# ESP32_mainboard.net
KiCad netlist of a schematic drawn in EAGLE
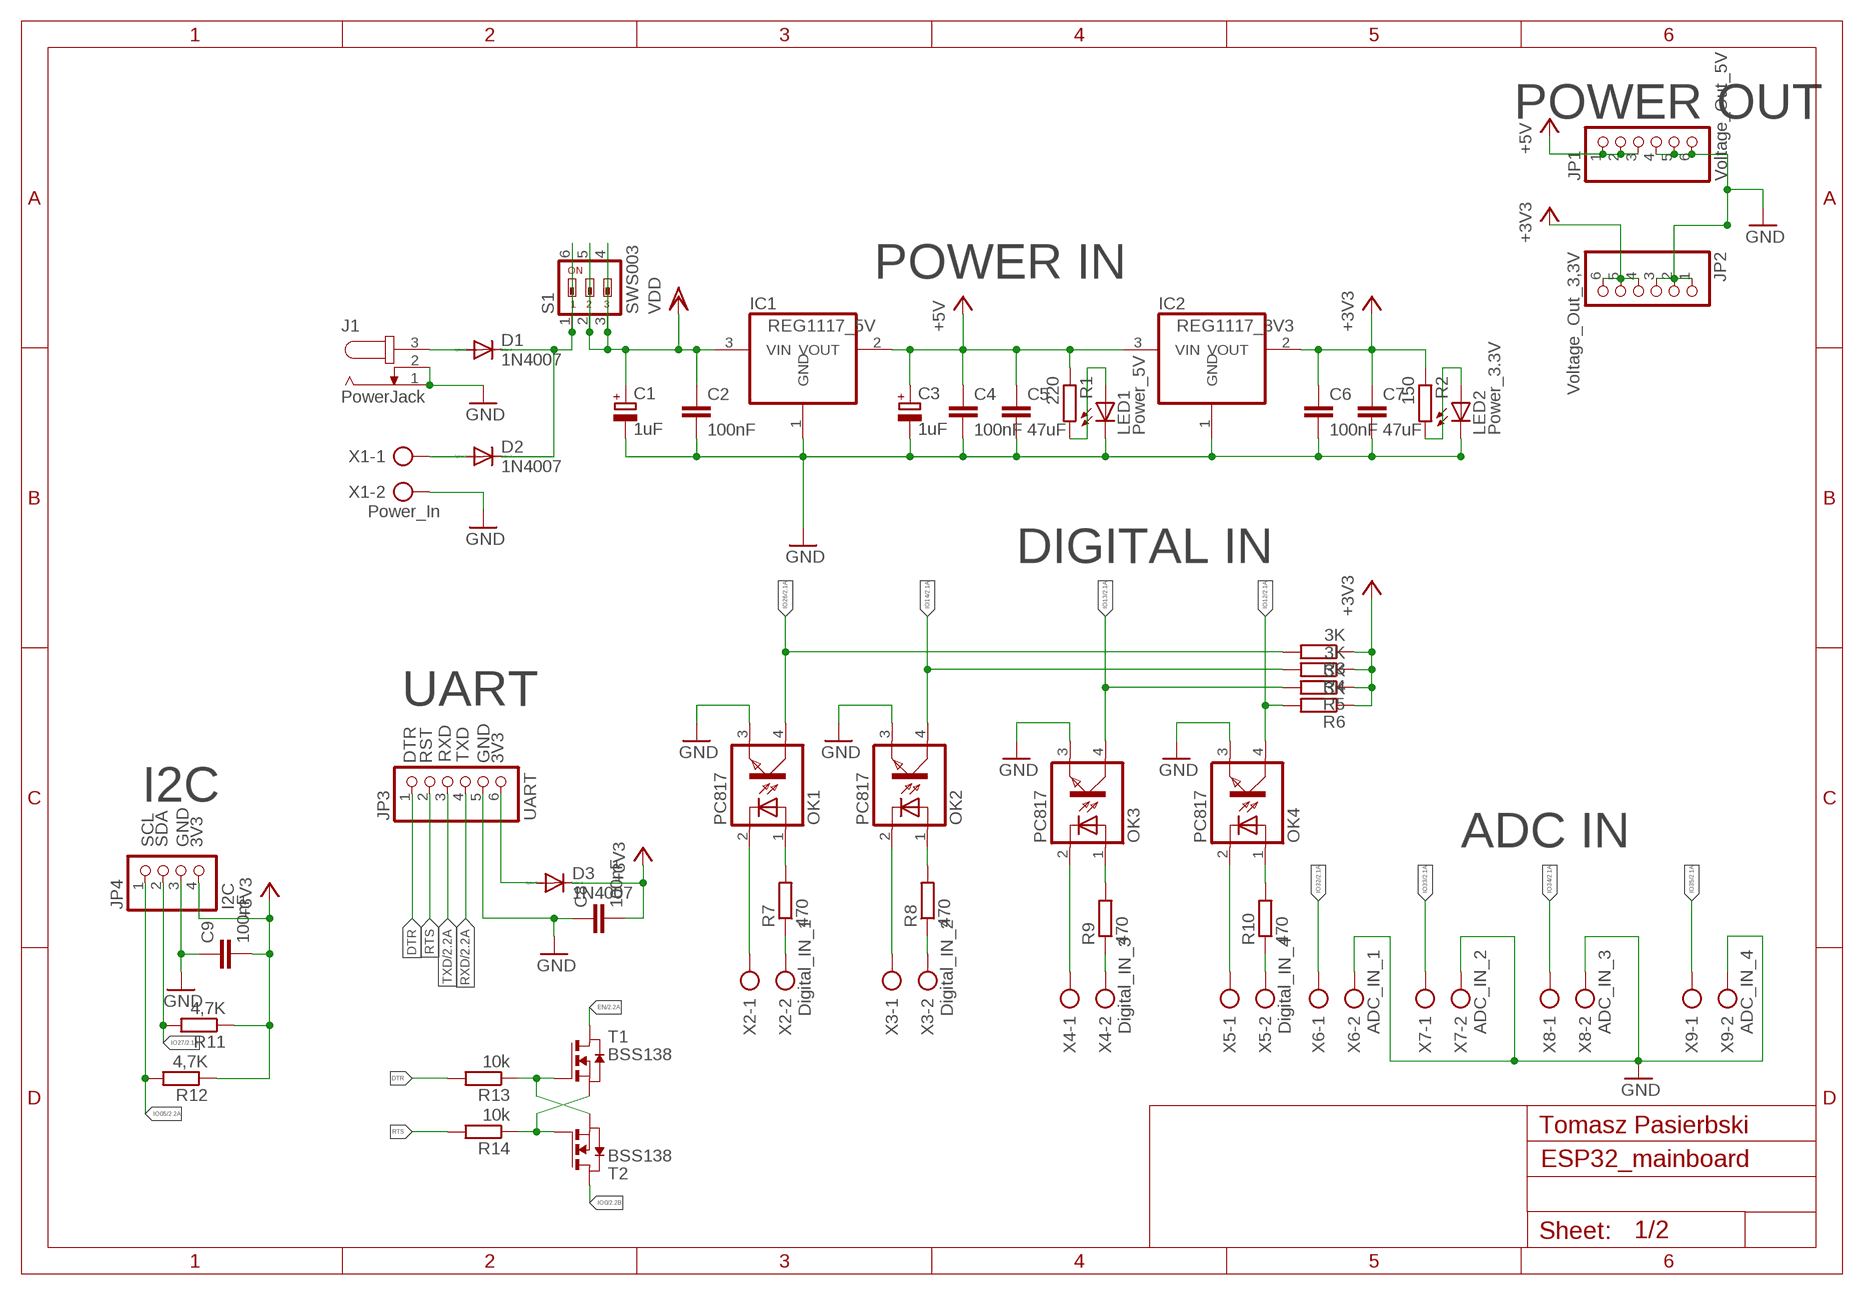
[diagram p0: schematic, sheet 1]
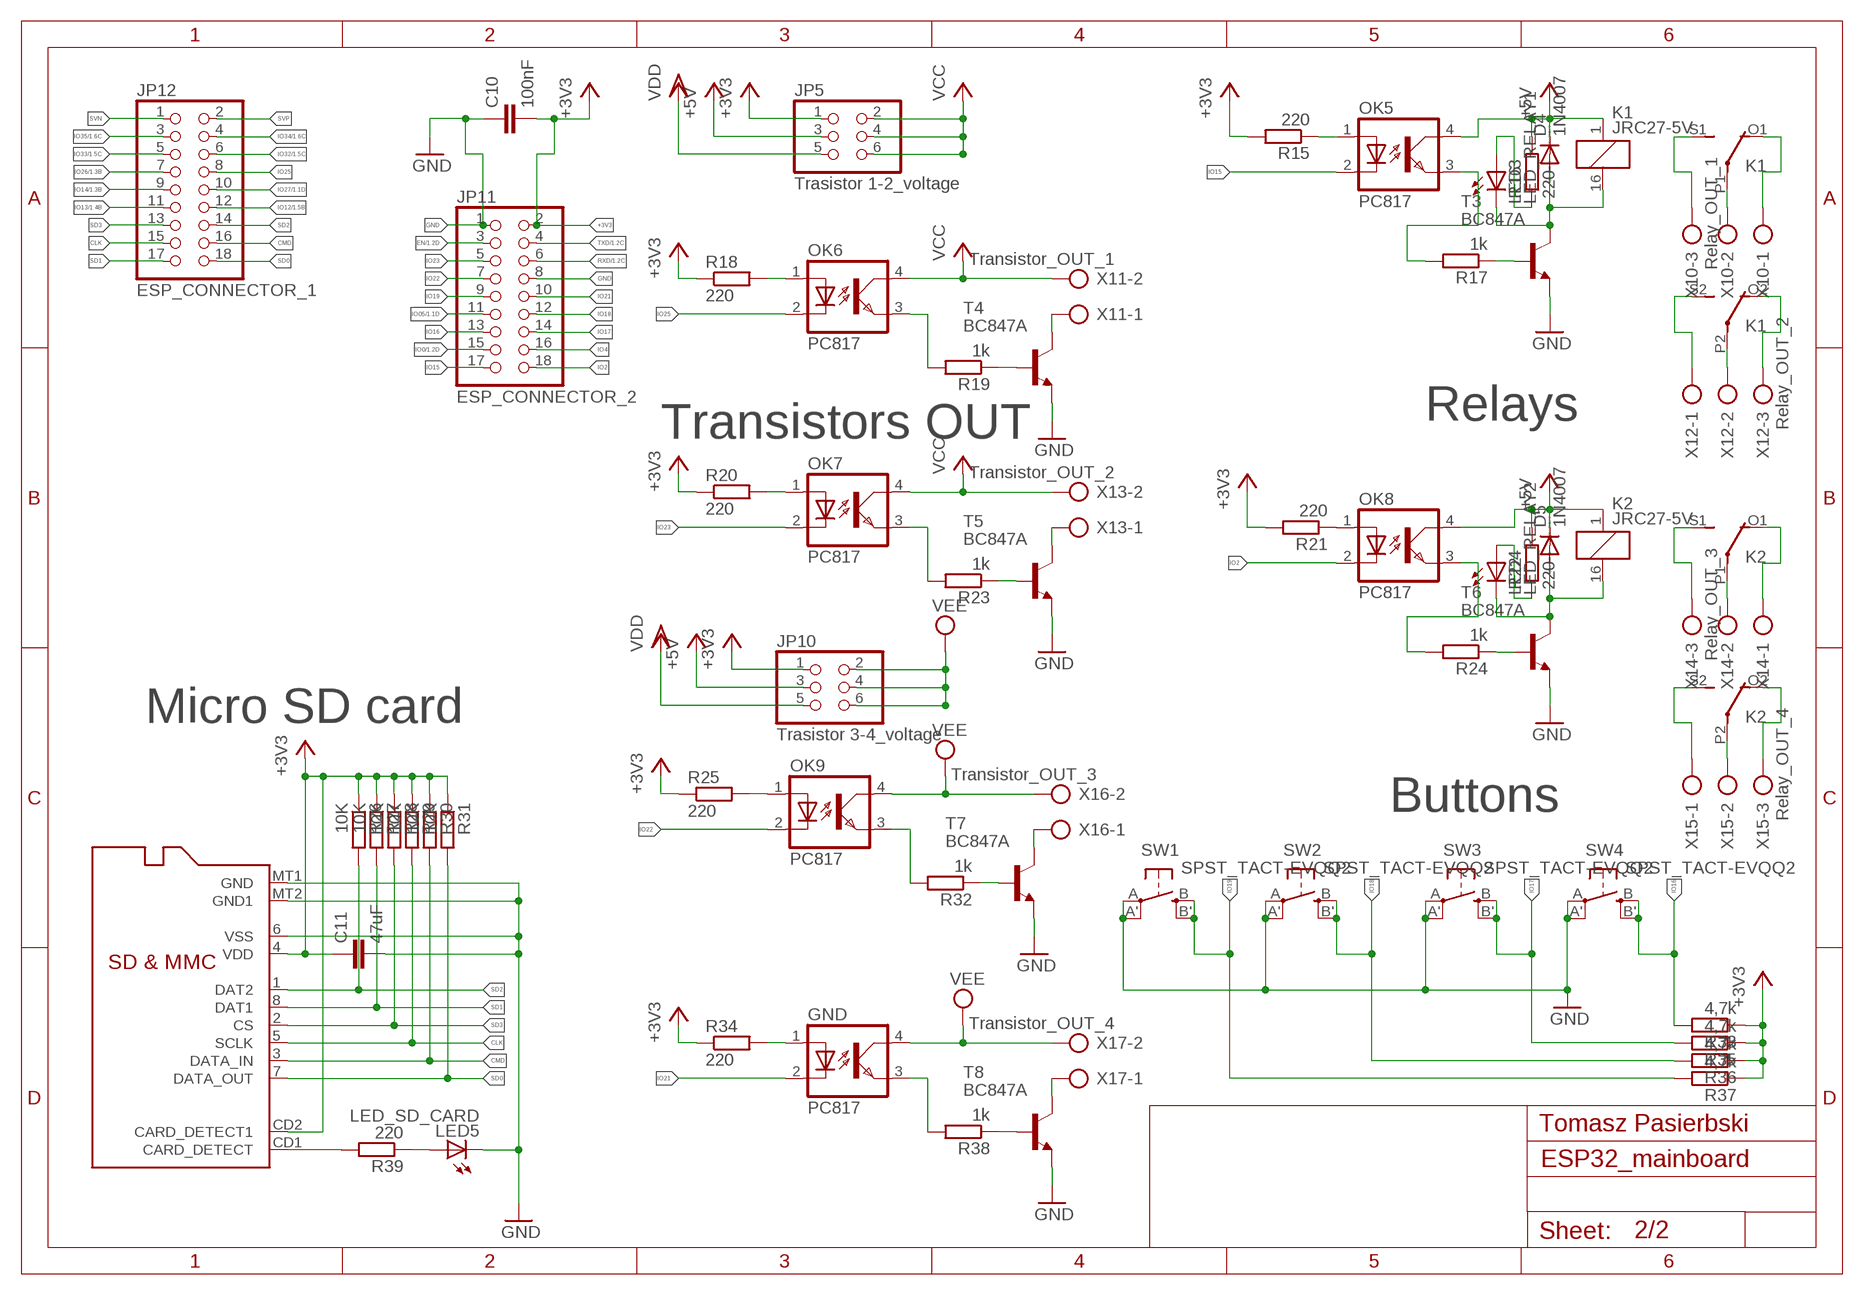
[diagram p1: schematic, sheet 2]

(export (version "E")
  (design (tool "Eeschema 10.0.6"))
  (components
    (comp (ref "C1")
      (value "1uF")
      (footprint "eagle-import:140CLH-0810")
      (libsource (lib "eagle-import") (part "CPOL-EU140CLH-0810"))
    )
    (comp (ref "C2")
      (value "100nF")
      (footprint "eagle-import:C1206")
      (libsource (lib "eagle-import") (part "C-EUC1206"))
    )
    (comp (ref "C3")
      (value "1uF")
      (footprint "eagle-import:140CLH-0810")
      (libsource (lib "eagle-import") (part "CPOL-EU140CLH-0810"))
    )
    (comp (ref "C4")
      (value "100nF")
      (footprint "eagle-import:C1206")
      (libsource (lib "eagle-import") (part "C-EUC1206"))
    )
    (comp (ref "C5")
      (value "47uF")
      (footprint "eagle-import:C1808")
      (libsource (lib "eagle-import") (part "C-EUC1808"))
    )
    (comp (ref "C6")
      (value "100nF")
      (footprint "eagle-import:C1206")
      (libsource (lib "eagle-import") (part "C-EUC1206"))
    )
    (comp (ref "C7")
      (value "47uF")
      (footprint "eagle-import:C1808")
      (libsource (lib "eagle-import") (part "C-EUC1808"))
    )
    (comp (ref "C8")
      (value "100nF")
      (footprint "eagle-import:C1206")
      (libsource (lib "eagle-import") (part "C-EUC1206"))
    )
    (comp (ref "C9")
      (value "100nF")
      (footprint "eagle-import:C1206")
      (libsource (lib "eagle-import") (part "C-EUC1206"))
    )
    (comp (ref "D1")
      (value "1N4007")
      (footprint "eagle-import:DO214AA")
      (libsource (lib "eagle-import") (part "DIODE-DO214AA"))
    )
    (comp (ref "D2")
      (value "1N4007")
      (footprint "eagle-import:DO214AA")
      (libsource (lib "eagle-import") (part "DIODE-DO214AA"))
    )
    (comp (ref "D3")
      (value "1N4007")
      (footprint "eagle-import:DO214AA")
      (libsource (lib "eagle-import") (part "DIODE-DO214AA"))
    )
    (comp (ref "IC1")
      (value "REG1117_5V")
      (footprint "eagle-import:SOT223")
      (fields (field (name "MPN") "REG1117"))
      (libsource (lib "eagle-import") (part "REG1117"))
    )
    (comp (ref "IC2")
      (value "REG1117_3V3")
      (footprint "eagle-import:SOT223")
      (fields (field (name "MPN") "REG1117"))
      (libsource (lib "eagle-import") (part "REG1117"))
    )
    (comp (ref "J1")
      (value "PowerJack")
      (footprint "eagle-import:SPC4077")
      (libsource (lib "eagle-import") (part "JACK-PLUG0"))
    )
    (comp (ref "JP1")
      (value "Voltage_Out_5V")
      (footprint "eagle-import:1X06_90")
      (libsource (lib "eagle-import") (part "PINHD-1X6/90"))
    )
    (comp (ref "JP2")
      (value "Voltage_Out_3,3V")
      (footprint "eagle-import:1X06_90")
      (libsource (lib "eagle-import") (part "PINHD-1X6/90"))
    )
    (comp (ref "JP3")
      (value "UART")
      (footprint "eagle-import:1X06_90")
      (libsource (lib "eagle-import") (part "PINHD-1X6/90"))
    )
    (comp (ref "JP4")
      (value "I2C")
      (footprint "eagle-import:1X04_90")
      (libsource (lib "eagle-import") (part "PINHD-1X4/90"))
    )
    (comp (ref "LED1")
      (value "Power_5V")
      (footprint "eagle-import:CHIPLED_1206")
      (libsource (lib "eagle-import") (part "LEDCHIPLED_1206"))
    )
    (comp (ref "LED2")
      (value "Power_3.3V")
      (footprint "eagle-import:CHIPLED_1206")
      (libsource (lib "eagle-import") (part "LEDCHIPLED_1206"))
    )
    (comp (ref "OK1")
      (value "PC817")
      (footprint "eagle-import:DIL04")
      (fields (field (name "MPN") "PC817X4J000F"))
      (libsource (lib "eagle-import") (part "PC817"))
    )
    (comp (ref "OK2")
      (value "PC817")
      (footprint "eagle-import:DIL04")
      (fields (field (name "MPN") "PC817X4J000F"))
      (libsource (lib "eagle-import") (part "PC817"))
    )
    (comp (ref "OK3")
      (value "PC817")
      (footprint "eagle-import:DIL04")
      (fields (field (name "MPN") "PC817X4J000F"))
      (libsource (lib "eagle-import") (part "PC817"))
    )
    (comp (ref "OK4")
      (value "PC817")
      (footprint "eagle-import:DIL04")
      (fields (field (name "MPN") "PC817X4J000F"))
      (libsource (lib "eagle-import") (part "PC817"))
    )
    (comp (ref "R1")
      (value "220")
      (footprint "eagle-import:M1206")
      (libsource (lib "eagle-import") (part "R-EU_M1206"))
    )
    (comp (ref "R2")
      (value "150")
      (footprint "eagle-import:M1206")
      (libsource (lib "eagle-import") (part "R-EU_M1206"))
    )
    (comp (ref "R3")
      (value "3K")
      (footprint "eagle-import:M1206")
      (libsource (lib "eagle-import") (part "R-EU_M1206"))
    )
    (comp (ref "R4")
      (value "3K")
      (footprint "eagle-import:M1206")
      (libsource (lib "eagle-import") (part "R-EU_M1206"))
    )
    (comp (ref "R5")
      (value "3K")
      (footprint "eagle-import:M1206")
      (libsource (lib "eagle-import") (part "R-EU_M1206"))
    )
    (comp (ref "R6")
      (value "3K")
      (footprint "eagle-import:M1206")
      (libsource (lib "eagle-import") (part "R-EU_M1206"))
    )
    (comp (ref "R7")
      (value "470")
      (footprint "eagle-import:M1206")
      (libsource (lib "eagle-import") (part "R-EU_M1206"))
    )
    (comp (ref "R8")
      (value "470")
      (footprint "eagle-import:M1206")
      (libsource (lib "eagle-import") (part "R-EU_M1206"))
    )
    (comp (ref "R9")
      (value "470")
      (footprint "eagle-import:M1206")
      (libsource (lib "eagle-import") (part "R-EU_M1206"))
    )
    (comp (ref "R10")
      (value "470")
      (footprint "eagle-import:M1206")
      (libsource (lib "eagle-import") (part "R-EU_M1206"))
    )
    (comp (ref "R11")
      (value "4,7K")
      (footprint "eagle-import:M1206")
      (libsource (lib "eagle-import") (part "R-EU_M1206"))
    )
    (comp (ref "R12")
      (value "4,7K")
      (footprint "eagle-import:M1206")
      (libsource (lib "eagle-import") (part "R-EU_M1206"))
    )
    (comp (ref "R13")
      (value "10k")
      (footprint "eagle-import:M1206")
      (libsource (lib "eagle-import") (part "R-EU_M1206"))
    )
    (comp (ref "R14")
      (value "10k")
      (footprint "eagle-import:M1206")
      (libsource (lib "eagle-import") (part "R-EU_M1206"))
    )
    (comp (ref "S1")
      (value "SWS003")
      (footprint "eagle-import:SMS-003")
      (libsource (lib "eagle-import") (part "SWS003"))
    )
    (comp (ref "T1")
      (value "BSS138")
      (footprint "eagle-import:SOT-23")
      (libsource (lib "eagle-import") (part "NMOSSOT23"))
    )
    (comp (ref "T2")
      (value "BSS138")
      (footprint "eagle-import:SOT-23")
      (libsource (lib "eagle-import") (part "NMOSSOT23"))
    )
    (comp (ref "X1")
      (value "Power_In")
      (footprint "eagle-import:AK300_2")
      (libsource (lib "eagle-import") (part "AK300/2"))
    )
    (comp (ref "X2")
      (value "Digital_IN_1")
      (footprint "eagle-import:AK300_2")
      (libsource (lib "eagle-import") (part "AK300/2"))
    )
    (comp (ref "X3")
      (value "Digital_IN_2")
      (footprint "eagle-import:AK300_2")
      (libsource (lib "eagle-import") (part "AK300/2"))
    )
    (comp (ref "X4")
      (value "Digital_IN_3")
      (footprint "eagle-import:AK300_2")
      (libsource (lib "eagle-import") (part "AK300/2"))
    )
    (comp (ref "X5")
      (value "Digital_IN_4")
      (footprint "eagle-import:AK300_2")
      (libsource (lib "eagle-import") (part "AK300/2"))
    )
    (comp (ref "X6")
      (value "ADC_IN_1")
      (footprint "eagle-import:AK300_2")
      (libsource (lib "eagle-import") (part "AK300/2"))
    )
    (comp (ref "X7")
      (value "ADC_IN_2")
      (footprint "eagle-import:AK300_2")
      (libsource (lib "eagle-import") (part "AK300/2"))
    )
    (comp (ref "X8")
      (value "ADC_IN_3")
      (footprint "eagle-import:AK300_2")
      (libsource (lib "eagle-import") (part "AK300/2"))
    )
    (comp (ref "X9")
      (value "ADC_IN_4")
      (footprint "eagle-import:AK300_2")
      (libsource (lib "eagle-import") (part "AK300/2"))
    )
    (comp (ref "C10")
      (value "100nF")
      (footprint "eagle-import:C1206")
      (libsource (lib "eagle-import") (part "C-EUC1206"))
    )
    (comp (ref "C11")
      (value "47uF")
      (footprint "eagle-import:C1808")
      (libsource (lib "eagle-import") (part "C-EUC1808"))
    )
    (comp (ref "D4")
      (value "1N4007")
      (footprint "eagle-import:DO214AC")
      (libsource (lib "eagle-import") (part "DIODE-DO214AC"))
    )
    (comp (ref "D5")
      (value "1N4007")
      (footprint "eagle-import:DO214AC")
      (libsource (lib "eagle-import") (part "DIODE-DO214AC"))
    )
    (comp (ref "GND")
      (value "PC817")
      (footprint "eagle-import:DIL04")
      (fields (field (name "MPN") "PC817X4J000F"))
      (libsource (lib "eagle-import") (part "PC817"))
    )
    (comp (ref "JP5")
      (value "Trasistor 1-2_voltage")
      (footprint "eagle-import:2X03")
      (libsource (lib "eagle-import") (part "PINHD-2X3"))
    )
    (comp (ref "JP10")
      (value "Trasistor 3-4_voltage")
      (footprint "eagle-import:2X03")
      (libsource (lib "eagle-import") (part "PINHD-2X3"))
    )
    (comp (ref "JP11")
      (value "ESP_CONNECTOR_2")
      (footprint "eagle-import:2X09")
      (libsource (lib "eagle-import") (part "PINHD-2X9"))
    )
    (comp (ref "JP12")
      (value "ESP_CONNECTOR_1")
      (footprint "eagle-import:2X09")
      (libsource (lib "eagle-import") (part "PINHD-2X9"))
    )
    (comp (ref "K1")
      (value "JRC27-5V")
      (footprint "eagle-import:351")
      (libsource (lib "eagle-import") (part "351"))
    )
    (comp (ref "K2")
      (value "JRC27-5V")
      (footprint "eagle-import:351")
      (libsource (lib "eagle-import") (part "351"))
    )
    (comp (ref "LED3")
      (value "LED_RELAY1")
      (footprint "eagle-import:CHIPLED_1206")
      (libsource (lib "eagle-import") (part "LEDCHIPLED_1206"))
    )
    (comp (ref "LED4")
      (value "LED_RELAY2")
      (footprint "eagle-import:CHIPLED_1206")
      (libsource (lib "eagle-import") (part "LEDCHIPLED_1206"))
    )
    (comp (ref "LED5")
      (value "LED_SD_CARD")
      (footprint "eagle-import:CHIPLED_1206")
      (libsource (lib "eagle-import") (part "LEDCHIPLED_1206"))
    )
    (comp (ref "OK5")
      (value "PC817")
      (footprint "eagle-import:DIL04")
      (fields (field (name "MPN") "PC817X4J000F"))
      (libsource (lib "eagle-import") (part "PC817"))
    )
    (comp (ref "OK6")
      (value "PC817")
      (footprint "eagle-import:DIL04")
      (fields (field (name "MPN") "PC817X4J000F"))
      (libsource (lib "eagle-import") (part "PC817"))
    )
    (comp (ref "OK7")
      (value "PC817")
      (footprint "eagle-import:DIL04")
      (fields (field (name "MPN") "PC817X4J000F"))
      (libsource (lib "eagle-import") (part "PC817"))
    )
    (comp (ref "OK8")
      (value "PC817")
      (footprint "eagle-import:DIL04")
      (fields (field (name "MPN") "PC817X4J000F"))
      (libsource (lib "eagle-import") (part "PC817"))
    )
    (comp (ref "OK9")
      (value "PC817")
      (footprint "eagle-import:DIL04")
      (fields (field (name "MPN") "PC817X4J000F"))
      (libsource (lib "eagle-import") (part "PC817"))
    )
    (comp (ref "R15")
      (value "220")
      (footprint "eagle-import:M1206")
      (libsource (lib "eagle-import") (part "R-EU_M1206"))
    )
    (comp (ref "R16")
      (value "220")
      (footprint "eagle-import:M1206")
      (libsource (lib "eagle-import") (part "R-EU_M1206"))
    )
    (comp (ref "R17")
      (value "1k")
      (footprint "eagle-import:M1206")
      (libsource (lib "eagle-import") (part "R-EU_M1206"))
    )
    (comp (ref "R18")
      (value "220")
      (footprint "eagle-import:M1206")
      (libsource (lib "eagle-import") (part "R-EU_M1206"))
    )
    (comp (ref "R19")
      (value "1k")
      (footprint "eagle-import:M1206")
      (libsource (lib "eagle-import") (part "R-EU_M1206"))
    )
    (comp (ref "R20")
      (value "220")
      (footprint "eagle-import:M1206")
      (libsource (lib "eagle-import") (part "R-EU_M1206"))
    )
    (comp (ref "R21")
      (value "220")
      (footprint "eagle-import:M1206")
      (libsource (lib "eagle-import") (part "R-EU_M1206"))
    )
    (comp (ref "R22")
      (value "220")
      (footprint "eagle-import:M1206")
      (libsource (lib "eagle-import") (part "R-EU_M1206"))
    )
    (comp (ref "R23")
      (value "1k")
      (footprint "eagle-import:M1206")
      (libsource (lib "eagle-import") (part "R-EU_M1206"))
    )
    (comp (ref "R24")
      (value "1k")
      (footprint "eagle-import:M1206")
      (libsource (lib "eagle-import") (part "R-EU_M1206"))
    )
    (comp (ref "R25")
      (value "220")
      (footprint "eagle-import:M1206")
      (libsource (lib "eagle-import") (part "R-EU_M1206"))
    )
    (comp (ref "R26")
      (value "10K")
      (footprint "eagle-import:M1206")
      (libsource (lib "eagle-import") (part "R-EU_M1206"))
    )
    (comp (ref "R27")
      (value "10K")
      (footprint "eagle-import:M1206")
      (libsource (lib "eagle-import") (part "R-EU_M1206"))
    )
    (comp (ref "R28")
      (value "10K")
      (footprint "eagle-import:M1206")
      (libsource (lib "eagle-import") (part "R-EU_M1206"))
    )
    (comp (ref "R29")
      (value "10K")
      (footprint "eagle-import:M1206")
      (libsource (lib "eagle-import") (part "R-EU_M1206"))
    )
    (comp (ref "R30")
      (value "10K")
      (footprint "eagle-import:M1206")
      (libsource (lib "eagle-import") (part "R-EU_M1206"))
    )
    (comp (ref "R31")
      (value "10K")
      (footprint "eagle-import:M1206")
      (libsource (lib "eagle-import") (part "R-EU_M1206"))
    )
    (comp (ref "R32")
      (value "1k")
      (footprint "eagle-import:M1206")
      (libsource (lib "eagle-import") (part "R-EU_M1206"))
    )
    (comp (ref "R33")
      (value "4,7k")
      (footprint "eagle-import:M1206")
      (libsource (lib "eagle-import") (part "R-EU_M1206"))
    )
    (comp (ref "R34")
      (value "220")
      (footprint "eagle-import:M1206")
      (libsource (lib "eagle-import") (part "R-EU_M1206"))
    )
    (comp (ref "R35")
      (value "4,7k")
      (footprint "eagle-import:M1206")
      (libsource (lib "eagle-import") (part "R-EU_M1206"))
    )
    (comp (ref "R36")
      (value "4,7k")
      (footprint "eagle-import:M1206")
      (libsource (lib "eagle-import") (part "R-EU_M1206"))
    )
    (comp (ref "R37")
      (value "4,7k")
      (footprint "eagle-import:M1206")
      (libsource (lib "eagle-import") (part "R-EU_M1206"))
    )
    (comp (ref "R38")
      (value "1k")
      (footprint "eagle-import:M1206")
      (libsource (lib "eagle-import") (part "R-EU_M1206"))
    )
    (comp (ref "R39")
      (value "220")
      (footprint "eagle-import:M1206")
      (libsource (lib "eagle-import") (part "R-EU_M1206"))
    )
    (comp (ref "SW1")
      (value "SPST_TACT-EVQQ2")
      (footprint "eagle-import:EVQ-Q2")
      (libsource (lib "eagle-import") (part "SPST_TACT-EVQQ2"))
    )
    (comp (ref "SW2")
      (value "SPST_TACT-EVQQ2")
      (footprint "eagle-import:EVQ-Q2")
      (libsource (lib "eagle-import") (part "SPST_TACT-EVQQ2"))
    )
    (comp (ref "SW3")
      (value "SPST_TACT-EVQQ2")
      (footprint "eagle-import:EVQ-Q2")
      (libsource (lib "eagle-import") (part "SPST_TACT-EVQQ2"))
    )
    (comp (ref "SW4")
      (value "SPST_TACT-EVQQ2")
      (footprint "eagle-import:EVQ-Q2")
      (libsource (lib "eagle-import") (part "SPST_TACT-EVQQ2"))
    )
    (comp (ref "T3")
      (value "BC847A")
      (footprint "eagle-import:SOT23-BEC")
      (libsource (lib "eagle-import") (part "-NPN-SOT23-BECBC847"))
    )
    (comp (ref "T4")
      (value "BC847A")
      (footprint "eagle-import:SOT23-BEC")
      (libsource (lib "eagle-import") (part "-NPN-SOT23-BECBC847"))
    )
    (comp (ref "T5")
      (value "BC847A")
      (footprint "eagle-import:SOT23-BEC")
      (libsource (lib "eagle-import") (part "-NPN-SOT23-BECBC847"))
    )
    (comp (ref "T6")
      (value "BC847A")
      (footprint "eagle-import:SOT23-BEC")
      (libsource (lib "eagle-import") (part "-NPN-SOT23-BECBC847"))
    )
    (comp (ref "T7")
      (value "BC847A")
      (footprint "eagle-import:SOT23-BEC")
      (libsource (lib "eagle-import") (part "-NPN-SOT23-BECBC847"))
    )
    (comp (ref "T8")
      (value "BC847A")
      (footprint "eagle-import:SOT23-BEC")
      (libsource (lib "eagle-import") (part "-NPN-SOT23-BECBC847"))
    )
    (comp (ref "U2")
      (value "MICROSD")
      (footprint "eagle-import:MICROSD")
      (libsource (lib "eagle-import") (part "MICROSD"))
    )
    (comp (ref "X10")
      (value "Relay_OUT_1")
      (footprint "eagle-import:AK300_3")
      (libsource (lib "eagle-import") (part "AK300/3"))
    )
    (comp (ref "X11")
      (value "Transistor_OUT_1")
      (footprint "eagle-import:AK300_2")
      (libsource (lib "eagle-import") (part "AK300/2"))
    )
    (comp (ref "X12")
      (value "Relay_OUT_2")
      (footprint "eagle-import:AK300_3")
      (libsource (lib "eagle-import") (part "AK300/3"))
    )
    (comp (ref "X13")
      (value "Transistor_OUT_2")
      (footprint "eagle-import:AK300_2")
      (libsource (lib "eagle-import") (part "AK300/2"))
    )
    (comp (ref "X14")
      (value "Relay_OUT_3")
      (footprint "eagle-import:AK300_3")
      (libsource (lib "eagle-import") (part "AK300/3"))
    )
    (comp (ref "X15")
      (value "Relay_OUT_4")
      (footprint "eagle-import:AK300_3")
      (libsource (lib "eagle-import") (part "AK300/3"))
    )
    (comp (ref "X16")
      (value "Transistor_OUT_3")
      (footprint "eagle-import:AK300_2")
      (libsource (lib "eagle-import") (part "AK300/2"))
    )
    (comp (ref "X17")
      (value "Transistor_OUT_4")
      (footprint "eagle-import:AK300_2")
      (libsource (lib "eagle-import") (part "AK300/2"))
    )
  )
  (nets
    (net (code "1") (name "+3V3") (class "Default")
      (node (ref "C10") (pin "2") (pinfunction "2_2") (pintype "passive"))
      (node (ref "C11") (pin "1") (pinfunction "1_1") (pintype "passive"))
      (node (ref "C6") (pin "1") (pinfunction "1_1") (pintype "passive"))
      (node (ref "C7") (pin "1") (pinfunction "1_1") (pintype "passive"))
      (node (ref "C8") (pin "2") (pinfunction "2_2") (pintype "passive"))
      (node (ref "C9") (pin "2") (pinfunction "2_2") (pintype "passive"))
      (node (ref "D3") (pin "C") (pinfunction "C_C") (pintype "passive"))
      (node (ref "IC2") (pin "2") (pinfunction "VOUT_2") (pintype "output"))
      (node (ref "JP10") (pin "1") (pinfunction "1_1") (pintype "passive"))
      (node (ref "JP11") (pin "2") (pinfunction "2_2") (pintype "passive"))
      (node (ref "JP2") (pin "4") (pinfunction "4_4") (pintype "passive"))
      (node (ref "JP2") (pin "5") (pinfunction "5_5") (pintype "passive"))
      (node (ref "JP2") (pin "6") (pinfunction "6_6") (pintype "passive"))
      (node (ref "JP4") (pin "4") (pinfunction "4_4") (pintype "passive"))
      (node (ref "JP5") (pin "1") (pinfunction "1_1") (pintype "passive"))
      (node (ref "R11") (pin "1") (pinfunction "1_1") (pintype "passive"))
      (node (ref "R12") (pin "1") (pinfunction "1_1") (pintype "passive"))
      (node (ref "R15") (pin "2") (pinfunction "2_2") (pintype "passive"))
      (node (ref "R18") (pin "1") (pinfunction "1_1") (pintype "passive"))
      (node (ref "R2") (pin "1") (pinfunction "1_1") (pintype "passive"))
      (node (ref "R20") (pin "1") (pinfunction "1_1") (pintype "passive"))
      (node (ref "R21") (pin "2") (pinfunction "2_2") (pintype "passive"))
      (node (ref "R25") (pin "1") (pinfunction "1_1") (pintype "passive"))
      (node (ref "R26") (pin "1") (pinfunction "1_1") (pintype "passive"))
      (node (ref "R27") (pin "1") (pinfunction "1_1") (pintype "passive"))
      (node (ref "R28") (pin "1") (pinfunction "1_1") (pintype "passive"))
      (node (ref "R29") (pin "1") (pinfunction "1_1") (pintype "passive"))
      (node (ref "R3") (pin "1") (pinfunction "1_1") (pintype "passive"))
      (node (ref "R30") (pin "1") (pinfunction "1_1") (pintype "passive"))
      (node (ref "R31") (pin "1") (pinfunction "1_1") (pintype "passive"))
      (node (ref "R33") (pin "1") (pinfunction "1_1") (pintype "passive"))
      (node (ref "R34") (pin "1") (pinfunction "1_1") (pintype "passive"))
      (node (ref "R35") (pin "1") (pinfunction "1_1") (pintype "passive"))
      (node (ref "R36") (pin "1") (pinfunction "1_1") (pintype "passive"))
      (node (ref "R37") (pin "1") (pinfunction "1_1") (pintype "passive"))
      (node (ref "R4") (pin "1") (pinfunction "1_1") (pintype "passive"))
      (node (ref "R5") (pin "1") (pinfunction "1_1") (pintype "passive"))
      (node (ref "R6") (pin "1") (pinfunction "1_1") (pintype "passive"))
      (node (ref "U2") (pin "4") (pinfunction "VDD_4") (pintype "power_in"))
      (node (ref "U2") (pin "CD2") (pinfunction "CARD_DETECT1_CD2") (pintype "passive"))
    )
    (net (code "2") (name "+5V") (class "Default")
      (node (ref "C3") (pin "+") (pinfunction "+_+") (pintype "passive"))
      (node (ref "C4") (pin "1") (pinfunction "1_1") (pintype "passive"))
      (node (ref "C5") (pin "1") (pinfunction "1_1") (pintype "passive"))
      (node (ref "D4") (pin "C") (pinfunction "C_C") (pintype "passive"))
      (node (ref "D5") (pin "C") (pinfunction "C_C") (pintype "passive"))
      (node (ref "IC1") (pin "2") (pinfunction "VOUT_2") (pintype "output"))
      (node (ref "IC2") (pin "3") (pinfunction "VIN_3") (pintype "input"))
      (node (ref "JP1") (pin "1") (pinfunction "1_1") (pintype "passive"))
      (node (ref "JP1") (pin "2") (pinfunction "2_2") (pintype "passive"))
      (node (ref "JP1") (pin "3") (pinfunction "3_3") (pintype "passive"))
      (node (ref "JP10") (pin "3") (pinfunction "3_3") (pintype "passive"))
      (node (ref "JP5") (pin "3") (pinfunction "3_3") (pintype "passive"))
      (node (ref "K1") (pin "1") (pinfunction "1_1") (pintype "passive"))
      (node (ref "K2") (pin "1") (pinfunction "1_1") (pintype "passive"))
      (node (ref "OK5") (pin "4") (pinfunction "COL_4") (pintype "passive"))
      (node (ref "OK8") (pin "4") (pinfunction "COL_4") (pintype "passive"))
      (node (ref "R1") (pin "1") (pinfunction "1_1") (pintype "passive"))
      (node (ref "R16") (pin "2") (pinfunction "2_2") (pintype "passive"))
      (node (ref "R22") (pin "2") (pinfunction "2_2") (pintype "passive"))
    )
    (net (code "3") (name "CLK") (class "Default")
      (node (ref "JP12") (pin "15") (pinfunction "15_15") (pintype "passive"))
      (node (ref "R29") (pin "2") (pinfunction "2_2") (pintype "passive"))
      (node (ref "U2") (pin "5") (pinfunction "SCLK_5") (pintype "input"))
    )
    (net (code "4") (name "CMD") (class "Default")
      (node (ref "JP12") (pin "16") (pinfunction "16_16") (pintype "passive"))
      (node (ref "R30") (pin "2") (pinfunction "2_2") (pintype "passive"))
      (node (ref "U2") (pin "3") (pinfunction "DATA_IN_3") (pintype "input"))
    )
    (net (code "5") (name "DTR") (class "Default")
      (node (ref "JP3") (pin "1") (pinfunction "1_1") (pintype "passive"))
      (node (ref "R13") (pin "2") (pinfunction "2_2") (pintype "passive"))
    )
    (net (code "6") (name "EN") (class "Default")
      (node (ref "JP11") (pin "3") (pinfunction "3_3") (pintype "passive"))
      (node (ref "T1") (pin "1") (pinfunction "D_1") (pintype "passive"))
    )
    (net (code "7") (name "GND") (class "Default")
      (node (ref "C1") (pin "-") (pinfunction "-_-") (pintype "passive"))
      (node (ref "C10") (pin "1") (pinfunction "1_1") (pintype "passive"))
      (node (ref "C11") (pin "2") (pinfunction "2_2") (pintype "passive"))
      (node (ref "C2") (pin "2") (pinfunction "2_2") (pintype "passive"))
      (node (ref "C3") (pin "-") (pinfunction "-_-") (pintype "passive"))
      (node (ref "C4") (pin "2") (pinfunction "2_2") (pintype "passive"))
      (node (ref "C5") (pin "2") (pinfunction "2_2") (pintype "passive"))
      (node (ref "C6") (pin "2") (pinfunction "2_2") (pintype "passive"))
      (node (ref "C7") (pin "2") (pinfunction "2_2") (pintype "passive"))
      (node (ref "C8") (pin "1") (pinfunction "1_1") (pintype "passive"))
      (node (ref "C9") (pin "1") (pinfunction "1_1") (pintype "passive"))
      (node (ref "IC1") (pin "1") (pinfunction "GND_1") (pintype "power_in"))
      (node (ref "IC2") (pin "1") (pinfunction "GND_1") (pintype "power_in"))
      (node (ref "J1") (pin "1") (pinfunction "1_1") (pintype "passive"))
      (node (ref "J1") (pin "2") (pinfunction "2_2") (pintype "passive"))
      (node (ref "JP1") (pin "4") (pinfunction "4_4") (pintype "passive"))
      (node (ref "JP1") (pin "5") (pinfunction "5_5") (pintype "passive"))
      (node (ref "JP1") (pin "6") (pinfunction "6_6") (pintype "passive"))
      (node (ref "JP11") (pin "1") (pinfunction "1_1") (pintype "passive"))
      (node (ref "JP11") (pin "8") (pinfunction "8_8") (pintype "passive"))
      (node (ref "JP2") (pin "1") (pinfunction "1_1") (pintype "passive"))
      (node (ref "JP2") (pin "2") (pinfunction "2_2") (pintype "passive"))
      (node (ref "JP2") (pin "3") (pinfunction "3_3") (pintype "passive"))
      (node (ref "JP3") (pin "5") (pinfunction "5_5") (pintype "passive"))
      (node (ref "JP4") (pin "3") (pinfunction "3_3") (pintype "passive"))
      (node (ref "LED1") (pin "C") (pinfunction "C_C") (pintype "passive"))
      (node (ref "LED2") (pin "C") (pinfunction "C_C") (pintype "passive"))
      (node (ref "LED5") (pin "C") (pinfunction "C_C") (pintype "passive"))
      (node (ref "OK1") (pin "3") (pinfunction "EMIT_3") (pintype "passive"))
      (node (ref "OK2") (pin "3") (pinfunction "EMIT_3") (pintype "passive"))
      (node (ref "OK3") (pin "3") (pinfunction "EMIT_3") (pintype "passive"))
      (node (ref "OK4") (pin "3") (pinfunction "EMIT_3") (pintype "passive"))
      (node (ref "SW1") (pin "A") (pinfunction "P_A") (pintype "passive"))
      (node (ref "SW1") (pin "A'") (pinfunction "P1_A'") (pintype "passive"))
      (node (ref "SW2") (pin "A") (pinfunction "P_A") (pintype "passive"))
      (node (ref "SW2") (pin "A'") (pinfunction "P1_A'") (pintype "passive"))
      (node (ref "SW3") (pin "A") (pinfunction "P_A") (pintype "passive"))
      (node (ref "SW3") (pin "A'") (pinfunction "P1_A'") (pintype "passive"))
      (node (ref "SW4") (pin "A") (pinfunction "P_A") (pintype "passive"))
      (node (ref "SW4") (pin "A'") (pinfunction "P1_A'") (pintype "passive"))
      (node (ref "T3") (pin "E") (pinfunction "E_E") (pintype "passive"))
      (node (ref "T4") (pin "E") (pinfunction "E_E") (pintype "passive"))
      (node (ref "T5") (pin "E") (pinfunction "E_E") (pintype "passive"))
      (node (ref "T6") (pin "E") (pinfunction "E_E") (pintype "passive"))
      (node (ref "T7") (pin "E") (pinfunction "E_E") (pintype "passive"))
      (node (ref "T8") (pin "E") (pinfunction "E_E") (pintype "passive"))
      (node (ref "U2") (pin "6") (pinfunction "VSS_6") (pintype "power_in"))
      (node (ref "U2") (pin "MT1") (pinfunction "GND_MT1") (pintype "power_in"))
      (node (ref "U2") (pin "MT2") (pinfunction "GND1_MT2") (pintype "power_in"))
      (node (ref "X1") (pin "2") (pinfunction "KL_2") (pintype "passive"))
      (node (ref "X6") (pin "2") (pinfunction "KL_2") (pintype "passive"))
      (node (ref "X7") (pin "2") (pinfunction "KL_2") (pintype "passive"))
      (node (ref "X8") (pin "2") (pinfunction "KL_2") (pintype "passive"))
      (node (ref "X9") (pin "2") (pinfunction "KL_2") (pintype "passive"))
    )
    (net (code "8") (name "IO0") (class "Default")
      (node (ref "JP11") (pin "15") (pinfunction "15_15") (pintype "passive"))
      (node (ref "T2") (pin "1") (pinfunction "D_1") (pintype "passive"))
    )
    (net (code "9") (name "IO2") (class "Default")
      (node (ref "JP11") (pin "18") (pinfunction "18_18") (pintype "passive"))
      (node (ref "OK8") (pin "2") (pinfunction "C_2") (pintype "passive"))
    )
    (net (code "10") (name "IO4") (class "Default")
      (node (ref "JP11") (pin "16") (pinfunction "16_16") (pintype "passive"))
    )
    (net (code "11") (name "IO05") (class "Default")
      (node (ref "JP11") (pin "11") (pinfunction "11_11") (pintype "passive"))
      (node (ref "JP4") (pin "1") (pinfunction "1_1") (pintype "passive"))
      (node (ref "R12") (pin "2") (pinfunction "2_2") (pintype "passive"))
    )
    (net (code "12") (name "IO12") (class "Default")
      (node (ref "JP12") (pin "12") (pinfunction "12_12") (pintype "passive"))
      (node (ref "OK4") (pin "4") (pinfunction "COL_4") (pintype "passive"))
      (node (ref "R6") (pin "2") (pinfunction "2_2") (pintype "passive"))
    )
    (net (code "13") (name "IO13") (class "Default")
      (node (ref "JP12") (pin "11") (pinfunction "11_11") (pintype "passive"))
      (node (ref "OK3") (pin "4") (pinfunction "COL_4") (pintype "passive"))
      (node (ref "R5") (pin "2") (pinfunction "2_2") (pintype "passive"))
    )
    (net (code "14") (name "IO14") (class "Default")
      (node (ref "JP12") (pin "9") (pinfunction "9_9") (pintype "passive"))
      (node (ref "OK2") (pin "4") (pinfunction "COL_4") (pintype "passive"))
      (node (ref "R4") (pin "2") (pinfunction "2_2") (pintype "passive"))
    )
    (net (code "15") (name "IO15") (class "Default")
      (node (ref "JP11") (pin "17") (pinfunction "17_17") (pintype "passive"))
      (node (ref "OK5") (pin "2") (pinfunction "C_2") (pintype "passive"))
    )
    (net (code "16") (name "IO16") (class "Default")
      (node (ref "JP11") (pin "13") (pinfunction "13_13") (pintype "passive"))
      (node (ref "R33") (pin "2") (pinfunction "2_2") (pintype "passive"))
      (node (ref "SW4") (pin "B") (pinfunction "S_B") (pintype "passive"))
      (node (ref "SW4") (pin "B'") (pinfunction "S1_B'") (pintype "passive"))
    )
    (net (code "17") (name "IO17") (class "Default")
      (node (ref "JP11") (pin "14") (pinfunction "14_14") (pintype "passive"))
      (node (ref "R35") (pin "2") (pinfunction "2_2") (pintype "passive"))
      (node (ref "SW3") (pin "B") (pinfunction "S_B") (pintype "passive"))
      (node (ref "SW3") (pin "B'") (pinfunction "S1_B'") (pintype "passive"))
    )
    (net (code "18") (name "IO18") (class "Default")
      (node (ref "JP11") (pin "12") (pinfunction "12_12") (pintype "passive"))
      (node (ref "R36") (pin "2") (pinfunction "2_2") (pintype "passive"))
      (node (ref "SW2") (pin "B") (pinfunction "S_B") (pintype "passive"))
      (node (ref "SW2") (pin "B'") (pinfunction "S1_B'") (pintype "passive"))
    )
    (net (code "19") (name "IO19") (class "Default")
      (node (ref "JP11") (pin "9") (pinfunction "9_9") (pintype "passive"))
      (node (ref "R37") (pin "2") (pinfunction "2_2") (pintype "passive"))
      (node (ref "SW1") (pin "B") (pinfunction "S_B") (pintype "passive"))
      (node (ref "SW1") (pin "B'") (pinfunction "S1_B'") (pintype "passive"))
    )
    (net (code "20") (name "IO21") (class "Default")
      (node (ref "GND") (pin "2") (pinfunction "C_2") (pintype "passive"))
      (node (ref "JP11") (pin "10") (pinfunction "10_10") (pintype "passive"))
    )
    (net (code "21") (name "IO22") (class "Default")
      (node (ref "JP11") (pin "7") (pinfunction "7_7") (pintype "passive"))
      (node (ref "OK9") (pin "2") (pinfunction "C_2") (pintype "passive"))
    )
    (net (code "22") (name "IO23") (class "Default")
      (node (ref "JP11") (pin "5") (pinfunction "5_5") (pintype "passive"))
      (node (ref "OK7") (pin "2") (pinfunction "C_2") (pintype "passive"))
    )
    (net (code "23") (name "IO25") (class "Default")
      (node (ref "JP12") (pin "8") (pinfunction "8_8") (pintype "passive"))
      (node (ref "OK6") (pin "2") (pinfunction "C_2") (pintype "passive"))
    )
    (net (code "24") (name "IO26") (class "Default")
      (node (ref "JP12") (pin "7") (pinfunction "7_7") (pintype "passive"))
      (node (ref "OK1") (pin "4") (pinfunction "COL_4") (pintype "passive"))
      (node (ref "R3") (pin "2") (pinfunction "2_2") (pintype "passive"))
    )
    (net (code "25") (name "IO27") (class "Default")
      (node (ref "JP12") (pin "10") (pinfunction "10_10") (pintype "passive"))
      (node (ref "JP4") (pin "2") (pinfunction "2_2") (pintype "passive"))
      (node (ref "R11") (pin "2") (pinfunction "2_2") (pintype "passive"))
    )
    (net (code "26") (name "IO32") (class "Default")
      (node (ref "JP12") (pin "6") (pinfunction "6_6") (pintype "passive"))
      (node (ref "X6") (pin "1") (pinfunction "KL_1") (pintype "passive"))
    )
    (net (code "27") (name "IO33") (class "Default")
      (node (ref "JP12") (pin "5") (pinfunction "5_5") (pintype "passive"))
      (node (ref "X7") (pin "1") (pinfunction "KL_1") (pintype "passive"))
    )
    (net (code "28") (name "IO34") (class "Default")
      (node (ref "JP12") (pin "4") (pinfunction "4_4") (pintype "passive"))
      (node (ref "X8") (pin "1") (pinfunction "KL_1") (pintype "passive"))
    )
    (net (code "29") (name "IO35") (class "Default")
      (node (ref "JP12") (pin "3") (pinfunction "3_3") (pintype "passive"))
      (node (ref "X9") (pin "1") (pinfunction "KL_1") (pintype "passive"))
    )
    (net (code "30") (name "Net-(D1-PadA)") (class "Default")
      (node (ref "D1") (pin "A") (pinfunction "A_A") (pintype "passive"))
      (node (ref "J1") (pin "3") (pinfunction "3_3") (pintype "passive"))
    )
    (net (code "31") (name "Net-(D1-PadC)") (class "Default")
      (node (ref "D1") (pin "C") (pinfunction "C_C") (pintype "passive"))
      (node (ref "D2") (pin "C") (pinfunction "C_C") (pintype "passive"))
      (node (ref "S1") (pin "1") (pinfunction "1_1") (pintype "passive"))
      (node (ref "S1") (pin "6") (pinfunction "6_6") (pintype "passive"))
    )
    (net (code "32") (name "Net-(D3-PadA)") (class "Default")
      (node (ref "D3") (pin "A") (pinfunction "A_A") (pintype "passive"))
      (node (ref "JP3") (pin "6") (pinfunction "6_6") (pintype "passive"))
    )
    (net (code "33") (name "Net-(GND-A)") (class "Default")
      (node (ref "GND") (pin "1") (pinfunction "A_1") (pintype "passive"))
      (node (ref "R34") (pin "2") (pinfunction "2_2") (pintype "passive"))
    )
    (net (code "34") (name "Net-(GND-EMIT)") (class "Default")
      (node (ref "GND") (pin "3") (pinfunction "EMIT_3") (pintype "passive"))
      (node (ref "R38") (pin "2") (pinfunction "2_2") (pintype "passive"))
    )
    (net (code "35") (name "Net-(K1A-2)") (class "Default")
      (node (ref "D4") (pin "A") (pinfunction "A_A") (pintype "passive"))
      (node (ref "K1") (pin "16") (pinfunction "2_16") (pintype "passive"))
      (node (ref "LED3") (pin "C") (pinfunction "C_C") (pintype "passive"))
      (node (ref "T3") (pin "C") (pinfunction "C_C") (pintype "passive"))
    )
    (net (code "36") (name "Net-(K1B-O)") (class "Default")
      (node (ref "K1") (pin "O1") (pinfunction "O_O1") (pintype "passive"))
      (node (ref "X10") (pin "1") (pinfunction "KL_1") (pintype "passive"))
    )
    (net (code "37") (name "Net-(K1B-P)") (class "Default")
      (node (ref "K1") (pin "P1") (pinfunction "P_P1") (pintype "passive"))
      (node (ref "X10") (pin "2") (pinfunction "KL_2") (pintype "passive"))
    )
    (net (code "38") (name "Net-(K1B-S)") (class "Default")
      (node (ref "K1") (pin "S1") (pinfunction "S_S1") (pintype "passive"))
      (node (ref "X10") (pin "3") (pinfunction "KL_3") (pintype "passive"))
    )
    (net (code "39") (name "Net-(K1C-O)") (class "Default")
      (node (ref "K1") (pin "O2") (pinfunction "O_O2") (pintype "passive"))
      (node (ref "X12") (pin "3") (pinfunction "KL_3") (pintype "passive"))
    )
    (net (code "40") (name "Net-(K1C-P)") (class "Default")
      (node (ref "K1") (pin "P2") (pinfunction "P_P2") (pintype "passive"))
      (node (ref "X12") (pin "2") (pinfunction "KL_2") (pintype "passive"))
    )
    (net (code "41") (name "Net-(K1C-S)") (class "Default")
      (node (ref "K1") (pin "S2") (pinfunction "S_S2") (pintype "passive"))
      (node (ref "X12") (pin "1") (pinfunction "KL_1") (pintype "passive"))
    )
    (net (code "42") (name "Net-(K2A-2)") (class "Default")
      (node (ref "D5") (pin "A") (pinfunction "A_A") (pintype "passive"))
      (node (ref "K2") (pin "16") (pinfunction "2_16") (pintype "passive"))
      (node (ref "LED4") (pin "C") (pinfunction "C_C") (pintype "passive"))
      (node (ref "T6") (pin "C") (pinfunction "C_C") (pintype "passive"))
    )
    (net (code "43") (name "Net-(K2B-O)") (class "Default")
      (node (ref "K2") (pin "O1") (pinfunction "O_O1") (pintype "passive"))
      (node (ref "X14") (pin "1") (pinfunction "KL_1") (pintype "passive"))
    )
    (net (code "44") (name "Net-(K2B-P)") (class "Default")
      (node (ref "K2") (pin "P1") (pinfunction "P_P1") (pintype "passive"))
      (node (ref "X14") (pin "2") (pinfunction "KL_2") (pintype "passive"))
    )
    (net (code "45") (name "Net-(K2B-S)") (class "Default")
      (node (ref "K2") (pin "S1") (pinfunction "S_S1") (pintype "passive"))
      (node (ref "X14") (pin "3") (pinfunction "KL_3") (pintype "passive"))
    )
    (net (code "46") (name "Net-(K2C-O)") (class "Default")
      (node (ref "K2") (pin "O2") (pinfunction "O_O2") (pintype "passive"))
      (node (ref "X15") (pin "3") (pinfunction "KL_3") (pintype "passive"))
    )
    (net (code "47") (name "Net-(K2C-P)") (class "Default")
      (node (ref "K2") (pin "P2") (pinfunction "P_P2") (pintype "passive"))
      (node (ref "X15") (pin "2") (pinfunction "KL_2") (pintype "passive"))
    )
    (net (code "48") (name "Net-(K2C-S)") (class "Default")
      (node (ref "K2") (pin "S2") (pinfunction "S_S2") (pintype "passive"))
      (node (ref "X15") (pin "1") (pinfunction "KL_1") (pintype "passive"))
    )
    (net (code "49") (name "Net-(LED1-PadA)") (class "Default")
      (node (ref "LED1") (pin "A") (pinfunction "A_A") (pintype "passive"))
      (node (ref "R1") (pin "2") (pinfunction "2_2") (pintype "passive"))
    )
    (net (code "50") (name "Net-(LED2-PadA)") (class "Default")
      (node (ref "LED2") (pin "A") (pinfunction "A_A") (pintype "passive"))
      (node (ref "R2") (pin "2") (pinfunction "2_2") (pintype "passive"))
    )
    (net (code "51") (name "Net-(LED3-PadA)") (class "Default")
      (node (ref "LED3") (pin "A") (pinfunction "A_A") (pintype "passive"))
      (node (ref "R16") (pin "1") (pinfunction "1_1") (pintype "passive"))
    )
    (net (code "52") (name "Net-(LED4-PadA)") (class "Default")
      (node (ref "LED4") (pin "A") (pinfunction "A_A") (pintype "passive"))
      (node (ref "R22") (pin "1") (pinfunction "1_1") (pintype "passive"))
    )
    (net (code "53") (name "Net-(LED5-PadA)") (class "Default")
      (node (ref "LED5") (pin "A") (pinfunction "A_A") (pintype "passive"))
      (node (ref "R39") (pin "1") (pinfunction "1_1") (pintype "passive"))
    )
    (net (code "54") (name "Net-(OK1-A)") (class "Default")
      (node (ref "OK1") (pin "1") (pinfunction "A_1") (pintype "passive"))
      (node (ref "R7") (pin "2") (pinfunction "2_2") (pintype "passive"))
    )
    (net (code "55") (name "Net-(OK1-C)") (class "Default")
      (node (ref "OK1") (pin "2") (pinfunction "C_2") (pintype "passive"))
      (node (ref "X2") (pin "1") (pinfunction "KL_1") (pintype "passive"))
    )
    (net (code "56") (name "Net-(OK2-A)") (class "Default")
      (node (ref "OK2") (pin "1") (pinfunction "A_1") (pintype "passive"))
      (node (ref "R8") (pin "2") (pinfunction "2_2") (pintype "passive"))
    )
    (net (code "57") (name "Net-(OK2-C)") (class "Default")
      (node (ref "OK2") (pin "2") (pinfunction "C_2") (pintype "passive"))
      (node (ref "X3") (pin "1") (pinfunction "KL_1") (pintype "passive"))
    )
    (net (code "58") (name "Net-(OK3-A)") (class "Default")
      (node (ref "OK3") (pin "1") (pinfunction "A_1") (pintype "passive"))
      (node (ref "R9") (pin "2") (pinfunction "2_2") (pintype "passive"))
    )
    (net (code "59") (name "Net-(OK3-C)") (class "Default")
      (node (ref "OK3") (pin "2") (pinfunction "C_2") (pintype "passive"))
      (node (ref "X4") (pin "1") (pinfunction "KL_1") (pintype "passive"))
    )
    (net (code "60") (name "Net-(OK4-A)") (class "Default")
      (node (ref "OK4") (pin "1") (pinfunction "A_1") (pintype "passive"))
      (node (ref "R10") (pin "2") (pinfunction "2_2") (pintype "passive"))
    )
    (net (code "61") (name "Net-(OK4-C)") (class "Default")
      (node (ref "OK4") (pin "2") (pinfunction "C_2") (pintype "passive"))
      (node (ref "X5") (pin "1") (pinfunction "KL_1") (pintype "passive"))
    )
    (net (code "62") (name "Net-(OK5-A)") (class "Default")
      (node (ref "OK5") (pin "1") (pinfunction "A_1") (pintype "passive"))
      (node (ref "R15") (pin "1") (pinfunction "1_1") (pintype "passive"))
    )
    (net (code "63") (name "Net-(OK5-EMIT)") (class "Default")
      (node (ref "OK5") (pin "3") (pinfunction "EMIT_3") (pintype "passive"))
      (node (ref "R17") (pin "2") (pinfunction "2_2") (pintype "passive"))
    )
    (net (code "64") (name "Net-(OK6-A)") (class "Default")
      (node (ref "OK6") (pin "1") (pinfunction "A_1") (pintype "passive"))
      (node (ref "R18") (pin "2") (pinfunction "2_2") (pintype "passive"))
    )
    (net (code "65") (name "Net-(OK6-EMIT)") (class "Default")
      (node (ref "OK6") (pin "3") (pinfunction "EMIT_3") (pintype "passive"))
      (node (ref "R19") (pin "2") (pinfunction "2_2") (pintype "passive"))
    )
    (net (code "66") (name "Net-(OK7-A)") (class "Default")
      (node (ref "OK7") (pin "1") (pinfunction "A_1") (pintype "passive"))
      (node (ref "R20") (pin "2") (pinfunction "2_2") (pintype "passive"))
    )
    (net (code "67") (name "Net-(OK7-EMIT)") (class "Default")
      (node (ref "OK7") (pin "3") (pinfunction "EMIT_3") (pintype "passive"))
      (node (ref "R23") (pin "2") (pinfunction "2_2") (pintype "passive"))
    )
    (net (code "68") (name "Net-(OK8-A)") (class "Default")
      (node (ref "OK8") (pin "1") (pinfunction "A_1") (pintype "passive"))
      (node (ref "R21") (pin "1") (pinfunction "1_1") (pintype "passive"))
    )
    (net (code "69") (name "Net-(OK8-EMIT)") (class "Default")
      (node (ref "OK8") (pin "3") (pinfunction "EMIT_3") (pintype "passive"))
      (node (ref "R24") (pin "2") (pinfunction "2_2") (pintype "passive"))
    )
    (net (code "70") (name "Net-(OK9-A)") (class "Default")
      (node (ref "OK9") (pin "1") (pinfunction "A_1") (pintype "passive"))
      (node (ref "R25") (pin "2") (pinfunction "2_2") (pintype "passive"))
    )
    (net (code "71") (name "Net-(OK9-EMIT)") (class "Default")
      (node (ref "OK9") (pin "3") (pinfunction "EMIT_3") (pintype "passive"))
      (node (ref "R32") (pin "2") (pinfunction "2_2") (pintype "passive"))
    )
    (net (code "72") (name "Net-(R17-Pad1)") (class "Default")
      (node (ref "R17") (pin "1") (pinfunction "1_1") (pintype "passive"))
      (node (ref "T3") (pin "B") (pinfunction "B_B") (pintype "passive"))
    )
    (net (code "73") (name "Net-(R19-Pad1)") (class "Default")
      (node (ref "R19") (pin "1") (pinfunction "1_1") (pintype "passive"))
      (node (ref "T4") (pin "B") (pinfunction "B_B") (pintype "passive"))
    )
    (net (code "74") (name "Net-(R23-Pad1)") (class "Default")
      (node (ref "R23") (pin "1") (pinfunction "1_1") (pintype "passive"))
      (node (ref "T5") (pin "B") (pinfunction "B_B") (pintype "passive"))
    )
    (net (code "75") (name "Net-(R24-Pad1)") (class "Default")
      (node (ref "R24") (pin "1") (pinfunction "1_1") (pintype "passive"))
      (node (ref "T6") (pin "B") (pinfunction "B_B") (pintype "passive"))
    )
    (net (code "76") (name "Net-(R32-Pad1)") (class "Default")
      (node (ref "R32") (pin "1") (pinfunction "1_1") (pintype "passive"))
      (node (ref "T7") (pin "B") (pinfunction "B_B") (pintype "passive"))
    )
    (net (code "77") (name "Net-(R38-Pad1)") (class "Default")
      (node (ref "R38") (pin "1") (pinfunction "1_1") (pintype "passive"))
      (node (ref "T8") (pin "B") (pinfunction "B_B") (pintype "passive"))
    )
    (net (code "78") (name "Net-(T1-G)") (class "Default")
      (node (ref "R13") (pin "1") (pinfunction "1_1") (pintype "passive"))
      (node (ref "T1") (pin "3") (pinfunction "G_3") (pintype "passive"))
      (node (ref "T2") (pin "2") (pinfunction "S_2") (pintype "passive"))
    )
    (net (code "79") (name "Net-(T1-S)") (class "Default")
      (node (ref "R14") (pin "1") (pinfunction "1_1") (pintype "passive"))
      (node (ref "T1") (pin "2") (pinfunction "S_2") (pintype "passive"))
      (node (ref "T2") (pin "3") (pinfunction "G_3") (pintype "passive"))
    )
    (net (code "80") (name "Net-(U2-CARD_DETECT)") (class "Default")
      (node (ref "R39") (pin "2") (pinfunction "2_2") (pintype "passive"))
      (node (ref "U2") (pin "CD1") (pinfunction "CARD_DETECT_CD1") (pintype "passive"))
    )
    (net (code "81") (name "Net-(X1A-KL)") (class "Default")
      (node (ref "D2") (pin "A") (pinfunction "A_A") (pintype "passive"))
      (node (ref "X1") (pin "1") (pinfunction "KL_1") (pintype "passive"))
    )
    (net (code "82") (name "Net-(X2B-KL)") (class "Default")
      (node (ref "R7") (pin "1") (pinfunction "1_1") (pintype "passive"))
      (node (ref "X2") (pin "2") (pinfunction "KL_2") (pintype "passive"))
    )
    (net (code "83") (name "Net-(X3B-KL)") (class "Default")
      (node (ref "R8") (pin "1") (pinfunction "1_1") (pintype "passive"))
      (node (ref "X3") (pin "2") (pinfunction "KL_2") (pintype "passive"))
    )
    (net (code "84") (name "Net-(X4B-KL)") (class "Default")
      (node (ref "R9") (pin "1") (pinfunction "1_1") (pintype "passive"))
      (node (ref "X4") (pin "2") (pinfunction "KL_2") (pintype "passive"))
    )
    (net (code "85") (name "Net-(X5B-KL)") (class "Default")
      (node (ref "R10") (pin "1") (pinfunction "1_1") (pintype "passive"))
      (node (ref "X5") (pin "2") (pinfunction "KL_2") (pintype "passive"))
    )
    (net (code "86") (name "Net-(X11A-KL)") (class "Default")
      (node (ref "T4") (pin "C") (pinfunction "C_C") (pintype "passive"))
      (node (ref "X11") (pin "1") (pinfunction "KL_1") (pintype "passive"))
    )
    (net (code "87") (name "Net-(X13A-KL)") (class "Default")
      (node (ref "T5") (pin "C") (pinfunction "C_C") (pintype "passive"))
      (node (ref "X13") (pin "1") (pinfunction "KL_1") (pintype "passive"))
    )
    (net (code "88") (name "Net-(X16A-KL)") (class "Default")
      (node (ref "T7") (pin "C") (pinfunction "C_C") (pintype "passive"))
      (node (ref "X16") (pin "1") (pinfunction "KL_1") (pintype "passive"))
    )
    (net (code "89") (name "Net-(X17A-KL)") (class "Default")
      (node (ref "T8") (pin "C") (pinfunction "C_C") (pintype "passive"))
      (node (ref "X17") (pin "1") (pinfunction "KL_1") (pintype "passive"))
    )
    (net (code "90") (name "RTS") (class "Default")
      (node (ref "JP3") (pin "2") (pinfunction "2_2") (pintype "passive"))
      (node (ref "R14") (pin "2") (pinfunction "2_2") (pintype "passive"))
    )
    (net (code "91") (name "RXD") (class "Default")
      (node (ref "JP11") (pin "6") (pinfunction "6_6") (pintype "passive"))
      (node (ref "JP3") (pin "4") (pinfunction "4_4") (pintype "passive"))
    )
    (net (code "92") (name "SD0") (class "Default")
      (node (ref "JP12") (pin "18") (pinfunction "18_18") (pintype "passive"))
      (node (ref "R31") (pin "2") (pinfunction "2_2") (pintype "passive"))
      (node (ref "U2") (pin "7") (pinfunction "DATA_OUT_7") (pintype "output"))
    )
    (net (code "93") (name "SD1") (class "Default")
      (node (ref "JP12") (pin "17") (pinfunction "17_17") (pintype "passive"))
      (node (ref "R27") (pin "2") (pinfunction "2_2") (pintype "passive"))
      (node (ref "U2") (pin "8") (pinfunction "DAT1_8") (pintype "bidirectional"))
    )
    (net (code "94") (name "SD2") (class "Default")
      (node (ref "JP12") (pin "14") (pinfunction "14_14") (pintype "passive"))
      (node (ref "R26") (pin "2") (pinfunction "2_2") (pintype "passive"))
      (node (ref "U2") (pin "1") (pinfunction "DAT2_1") (pintype "bidirectional"))
    )
    (net (code "95") (name "SD3") (class "Default")
      (node (ref "JP12") (pin "13") (pinfunction "13_13") (pintype "passive"))
      (node (ref "R28") (pin "2") (pinfunction "2_2") (pintype "passive"))
      (node (ref "U2") (pin "2") (pinfunction "CS_2") (pintype "input"))
    )
    (net (code "96") (name "SVN") (class "Default")
      (node (ref "JP12") (pin "1") (pinfunction "1_1") (pintype "passive"))
    )
    (net (code "97") (name "SVP") (class "Default")
      (node (ref "JP12") (pin "2") (pinfunction "2_2") (pintype "passive"))
    )
    (net (code "98") (name "TXD") (class "Default")
      (node (ref "JP11") (pin "4") (pinfunction "4_4") (pintype "passive"))
      (node (ref "JP3") (pin "3") (pinfunction "3_3") (pintype "passive"))
    )
    (net (code "99") (name "VCC") (class "Default")
      (node (ref "JP5") (pin "2") (pinfunction "2_2") (pintype "passive"))
      (node (ref "JP5") (pin "4") (pinfunction "4_4") (pintype "passive"))
      (node (ref "JP5") (pin "6") (pinfunction "6_6") (pintype "passive"))
      (node (ref "OK6") (pin "4") (pinfunction "COL_4") (pintype "passive"))
      (node (ref "OK7") (pin "4") (pinfunction "COL_4") (pintype "passive"))
      (node (ref "X11") (pin "2") (pinfunction "KL_2") (pintype "passive"))
      (node (ref "X13") (pin "2") (pinfunction "KL_2") (pintype "passive"))
    )
    (net (code "100") (name "VDD") (class "Default")
      (node (ref "C1") (pin "+") (pinfunction "+_+") (pintype "passive"))
      (node (ref "C2") (pin "1") (pinfunction "1_1") (pintype "passive"))
      (node (ref "IC1") (pin "3") (pinfunction "VIN_3") (pintype "input"))
      (node (ref "JP10") (pin "5") (pinfunction "5_5") (pintype "passive"))
      (node (ref "JP5") (pin "5") (pinfunction "5_5") (pintype "passive"))
      (node (ref "S1") (pin "2") (pinfunction "2_2") (pintype "passive"))
      (node (ref "S1") (pin "3") (pinfunction "3_3") (pintype "passive"))
      (node (ref "S1") (pin "4") (pinfunction "4_4") (pintype "passive"))
      (node (ref "S1") (pin "5") (pinfunction "5_5") (pintype "passive"))
    )
    (net (code "101") (name "VEE") (class "Default")
      (node (ref "GND") (pin "4") (pinfunction "COL_4") (pintype "passive"))
      (node (ref "JP10") (pin "2") (pinfunction "2_2") (pintype "passive"))
      (node (ref "JP10") (pin "4") (pinfunction "4_4") (pintype "passive"))
      (node (ref "JP10") (pin "6") (pinfunction "6_6") (pintype "passive"))
      (node (ref "OK9") (pin "4") (pinfunction "COL_4") (pintype "passive"))
      (node (ref "X16") (pin "2") (pinfunction "KL_2") (pintype "passive"))
      (node (ref "X17") (pin "2") (pinfunction "KL_2") (pintype "passive"))
    )
  )
)
